# cube_atmega328.net
KiCad netlist of a schematic drawn in EAGLE
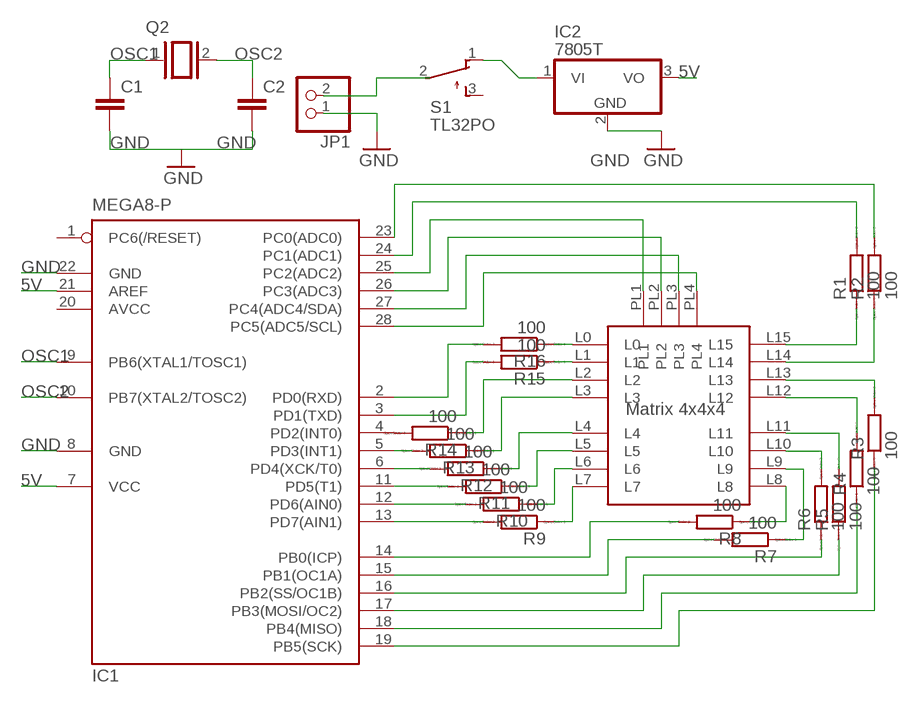
[diagram p0: schematic, sheet 1]

(export (version "E")
  (design (tool "Eeschema 10.0.6"))
  (components
    (comp (ref "C1")
      (value "C5/2.5")
      (footprint "eagle-import:C5B2.5")
      (libsource (lib "eagle-import") (part "C5/2.5"))
    )
    (comp (ref "C2")
      (value "C5/2.5")
      (footprint "eagle-import:C5B2.5")
      (libsource (lib "eagle-import") (part "C5/2.5"))
    )
    (comp (ref "IC1")
      (value "MEGA8-P")
      (footprint "eagle-import:DIL28-3")
      (libsource (lib "eagle-import") (part "MEGA8-P"))
    )
    (comp (ref "IC2")
      (value "7805T")
      (footprint "eagle-import:TO220H")
      (libsource (lib "eagle-import") (part "78T05"))
    )
    (comp (ref "JP1")
      (value "PINHD-1X2")
      (footprint "eagle-import:1X02")
      (libsource (lib "eagle-import") (part "PINHD-1X2"))
    )
    (comp (ref "Q2")
      (value "XTAL/S")
      (footprint "eagle-import:QS")
      (libsource (lib "eagle-import") (part "XTAL/S"))
    )
    (comp (ref "R1")
      (value "100")
      (footprint "eagle-import:0207_10")
      (libsource (lib "eagle-import") (part "R0207/10"))
    )
    (comp (ref "R2")
      (value "100")
      (footprint "eagle-import:0207_10")
      (libsource (lib "eagle-import") (part "R0207/10"))
    )
    (comp (ref "R3")
      (value "100")
      (footprint "eagle-import:0207_10")
      (libsource (lib "eagle-import") (part "R0207/10"))
    )
    (comp (ref "R4")
      (value "100")
      (footprint "eagle-import:0207_10")
      (libsource (lib "eagle-import") (part "R0207/10"))
    )
    (comp (ref "R5")
      (value "100")
      (footprint "eagle-import:0207_10")
      (libsource (lib "eagle-import") (part "R0207/10"))
    )
    (comp (ref "R6")
      (value "100")
      (footprint "eagle-import:0207_10")
      (libsource (lib "eagle-import") (part "R0207/10"))
    )
    (comp (ref "R7")
      (value "100")
      (footprint "eagle-import:0207_10")
      (libsource (lib "eagle-import") (part "R0207/10"))
    )
    (comp (ref "R8")
      (value "100")
      (footprint "eagle-import:0207_10")
      (libsource (lib "eagle-import") (part "R0207/10"))
    )
    (comp (ref "R9")
      (value "100")
      (footprint "eagle-import:0207_10")
      (libsource (lib "eagle-import") (part "R0207/10"))
    )
    (comp (ref "R10")
      (value "100")
      (footprint "eagle-import:0207_10")
      (libsource (lib "eagle-import") (part "R0207/10"))
    )
    (comp (ref "R11")
      (value "100")
      (footprint "eagle-import:0207_10")
      (libsource (lib "eagle-import") (part "R0207/10"))
    )
    (comp (ref "R12")
      (value "100")
      (footprint "eagle-import:0207_10")
      (libsource (lib "eagle-import") (part "R0207/10"))
    )
    (comp (ref "R13")
      (value "100")
      (footprint "eagle-import:0207_10")
      (libsource (lib "eagle-import") (part "R0207/10"))
    )
    (comp (ref "R14")
      (value "100")
      (footprint "eagle-import:0207_10")
      (libsource (lib "eagle-import") (part "R0207/10"))
    )
    (comp (ref "R15")
      (value "100")
      (footprint "eagle-import:0207_10")
      (libsource (lib "eagle-import") (part "R0207/10"))
    )
    (comp (ref "R16")
      (value "100")
      (footprint "eagle-import:0207_10")
      (libsource (lib "eagle-import") (part "R0207/10"))
    )
    (comp (ref "S1")
      (value "TL32PO")
      (footprint "eagle-import:TL3XPO")
      (libsource (lib "eagle-import") (part "TL32PO"))
    )
    (comp (ref "U$1")
      (value "LC4X4X4")
      (footprint "eagle-import:LC4X4X4")
      (libsource (lib "eagle-import") (part "LC4X4X4"))
    )
  )
  (nets
    (net (code "1") (name "/5V") (class "Default")
      (node (ref "IC1") (pin "21") (pinfunction "AREF_21") (pintype "passive"))
      (node (ref "IC1") (pin "7") (pinfunction "VCC_7") (pintype "power_in"))
      (node (ref "IC2") (pin "3") (pinfunction "VO_3") (pintype "passive"))
    )
    (net (code "2") (name "/AVCC") (class "Default")
      (node (ref "IC1") (pin "20") (pinfunction "AVCC_20") (pintype "power_in"))
    )
    (net (code "3") (name "/OSC1") (class "Default")
      (node (ref "C1") (pin "1") (pinfunction "1_1") (pintype "passive"))
      (node (ref "IC1") (pin "9") (pinfunction "PB6(XTAL1/TOSC1)_9") (pintype "bidirectional"))
      (node (ref "Q2") (pin "1") (pinfunction "1_1") (pintype "passive"))
    )
    (net (code "4") (name "/OSC2") (class "Default")
      (node (ref "C2") (pin "1") (pinfunction "1_1") (pintype "passive"))
      (node (ref "IC1") (pin "10") (pinfunction "PB7(XTAL2/TOSC2)_10") (pintype "bidirectional"))
      (node (ref "Q2") (pin "2") (pinfunction "2_2") (pintype "passive"))
    )
    (net (code "5") (name "GND") (class "Default")
      (node (ref "C1") (pin "2") (pinfunction "2_2") (pintype "passive"))
      (node (ref "C2") (pin "2") (pinfunction "2_2") (pintype "passive"))
      (node (ref "IC1") (pin "22") (pinfunction "GND_22") (pintype "power_in"))
      (node (ref "IC1") (pin "8") (pinfunction "GND_8") (pintype "power_in"))
      (node (ref "IC2") (pin "2") (pinfunction "GND_2") (pintype "passive"))
      (node (ref "JP1") (pin "1") (pinfunction "1_1") (pintype "passive"))
    )
    (net (code "6") (name "Net-(IC1-PB0(ICP))") (class "Default")
      (node (ref "IC1") (pin "14") (pinfunction "PB0(ICP)_14") (pintype "bidirectional"))
      (node (ref "R8") (pin "2") (pinfunction "2_2") (pintype "passive"))
    )
    (net (code "7") (name "Net-(IC1-PB1(OC1A))") (class "Default")
      (node (ref "IC1") (pin "15") (pinfunction "PB1(OC1A)_15") (pintype "bidirectional"))
      (node (ref "R7") (pin "2") (pinfunction "2_2") (pintype "passive"))
    )
    (net (code "8") (name "Net-(IC1-PB2(SS{slash}OC1B))") (class "Default")
      (node (ref "IC1") (pin "16") (pinfunction "PB2(SS/OC1B)_16") (pintype "bidirectional"))
      (node (ref "R6") (pin "1") (pinfunction "1_1") (pintype "passive"))
    )
    (net (code "9") (name "Net-(IC1-PB3(MOSI{slash}OC2))") (class "Default")
      (node (ref "IC1") (pin "17") (pinfunction "PB3(MOSI/OC2)_17") (pintype "bidirectional"))
      (node (ref "R5") (pin "1") (pinfunction "1_1") (pintype "passive"))
    )
    (net (code "10") (name "Net-(IC1-PB4(MISO))") (class "Default")
      (node (ref "IC1") (pin "18") (pinfunction "PB4(MISO)_18") (pintype "bidirectional"))
      (node (ref "R4") (pin "1") (pinfunction "1_1") (pintype "passive"))
    )
    (net (code "11") (name "Net-(IC1-PB5(SCK))") (class "Default")
      (node (ref "IC1") (pin "19") (pinfunction "PB5(SCK)_19") (pintype "bidirectional"))
      (node (ref "R3") (pin "1") (pinfunction "1_1") (pintype "passive"))
    )
    (net (code "12") (name "Net-(IC1-PC0(ADC0))") (class "Default")
      (node (ref "IC1") (pin "23") (pinfunction "PC0(ADC0)_23") (pintype "bidirectional"))
      (node (ref "R2") (pin "2") (pinfunction "2_2") (pintype "passive"))
    )
    (net (code "13") (name "Net-(IC1-PC1(ADC1))") (class "Default")
      (node (ref "IC1") (pin "24") (pinfunction "PC1(ADC1)_24") (pintype "bidirectional"))
      (node (ref "R1") (pin "2") (pinfunction "2_2") (pintype "passive"))
    )
    (net (code "14") (name "Net-(IC1-PC2(ADC2))") (class "Default")
      (node (ref "IC1") (pin "25") (pinfunction "PC2(ADC2)_25") (pintype "bidirectional"))
      (node (ref "U$1") (pin "PL1") (pinfunction "PL1_PL1") (pintype "bidirectional"))
    )
    (net (code "15") (name "Net-(IC1-PC3(ADC3))") (class "Default")
      (node (ref "IC1") (pin "26") (pinfunction "PC3(ADC3)_26") (pintype "bidirectional"))
      (node (ref "U$1") (pin "PL2") (pinfunction "PL2_PL2") (pintype "bidirectional"))
    )
    (net (code "16") (name "Net-(IC1-PC4(ADC4{slash}SDA))") (class "Default")
      (node (ref "IC1") (pin "27") (pinfunction "PC4(ADC4/SDA)_27") (pintype "bidirectional"))
      (node (ref "U$1") (pin "PL3") (pinfunction "PL3_PL3") (pintype "bidirectional"))
    )
    (net (code "17") (name "Net-(IC1-PC5(ADC5{slash}SCL))") (class "Default")
      (node (ref "IC1") (pin "28") (pinfunction "PC5(ADC5/SCL)_28") (pintype "bidirectional"))
      (node (ref "U$1") (pin "PL4") (pinfunction "PL4_PL4") (pintype "bidirectional"))
    )
    (net (code "18") (name "Net-(IC1-PD0(RXD))") (class "Default")
      (node (ref "IC1") (pin "2") (pinfunction "PD0(RXD)_2") (pintype "bidirectional"))
      (node (ref "R16") (pin "2") (pinfunction "2_2") (pintype "passive"))
    )
    (net (code "19") (name "Net-(IC1-PD1(TXD))") (class "Default")
      (node (ref "IC1") (pin "3") (pinfunction "PD1(TXD)_3") (pintype "bidirectional"))
      (node (ref "R15") (pin "2") (pinfunction "2_2") (pintype "passive"))
    )
    (net (code "20") (name "Net-(IC1-PD2(INT0))") (class "Default")
      (node (ref "IC1") (pin "4") (pinfunction "PD2(INT0)_4") (pintype "bidirectional"))
      (node (ref "R14") (pin "2") (pinfunction "2_2") (pintype "passive"))
    )
    (net (code "21") (name "Net-(IC1-PD3(INT1))") (class "Default")
      (node (ref "IC1") (pin "5") (pinfunction "PD3(INT1)_5") (pintype "bidirectional"))
      (node (ref "R13") (pin "2") (pinfunction "2_2") (pintype "passive"))
    )
    (net (code "22") (name "Net-(IC1-PD4(XCK{slash}T0))") (class "Default")
      (node (ref "IC1") (pin "6") (pinfunction "PD4(XCK/T0)_6") (pintype "bidirectional"))
      (node (ref "R12") (pin "2") (pinfunction "2_2") (pintype "passive"))
    )
    (net (code "23") (name "Net-(IC1-PD5(T1))") (class "Default")
      (node (ref "IC1") (pin "11") (pinfunction "PD5(T1)_11") (pintype "bidirectional"))
      (node (ref "R11") (pin "2") (pinfunction "2_2") (pintype "passive"))
    )
    (net (code "24") (name "Net-(IC1-PD6(AIN0))") (class "Default")
      (node (ref "IC1") (pin "12") (pinfunction "PD6(AIN0)_12") (pintype "bidirectional"))
      (node (ref "R10") (pin "2") (pinfunction "2_2") (pintype "passive"))
    )
    (net (code "25") (name "Net-(IC1-PD7(AIN1))") (class "Default")
      (node (ref "IC1") (pin "13") (pinfunction "PD7(AIN1)_13") (pintype "bidirectional"))
      (node (ref "R9") (pin "2") (pinfunction "2_2") (pintype "passive"))
    )
    (net (code "26") (name "Net-(IC2-VI)") (class "Default")
      (node (ref "IC2") (pin "1") (pinfunction "VI_1") (pintype "input"))
      (node (ref "S1") (pin "1") (pinfunction "O_1") (pintype "passive"))
    )
    (net (code "27") (name "Net-(R1-Pad1)") (class "Default")
      (node (ref "R1") (pin "1") (pinfunction "1_1") (pintype "passive"))
      (node (ref "U$1") (pin "L15") (pinfunction "L15_L15") (pintype "bidirectional"))
    )
    (net (code "28") (name "Net-(R2-Pad1)") (class "Default")
      (node (ref "R2") (pin "1") (pinfunction "1_1") (pintype "passive"))
      (node (ref "U$1") (pin "L14") (pinfunction "L14_L14") (pintype "bidirectional"))
    )
    (net (code "29") (name "Net-(R3-Pad2)") (class "Default")
      (node (ref "R3") (pin "2") (pinfunction "2_2") (pintype "passive"))
      (node (ref "U$1") (pin "L13") (pinfunction "L13_L13") (pintype "bidirectional"))
    )
    (net (code "30") (name "Net-(R4-Pad2)") (class "Default")
      (node (ref "R4") (pin "2") (pinfunction "2_2") (pintype "passive"))
      (node (ref "U$1") (pin "L12") (pinfunction "L12_L12") (pintype "bidirectional"))
    )
    (net (code "31") (name "Net-(R5-Pad2)") (class "Default")
      (node (ref "R5") (pin "2") (pinfunction "2_2") (pintype "passive"))
      (node (ref "U$1") (pin "L11") (pinfunction "L11_L11") (pintype "bidirectional"))
    )
    (net (code "32") (name "Net-(R6-Pad2)") (class "Default")
      (node (ref "R6") (pin "2") (pinfunction "2_2") (pintype "passive"))
      (node (ref "U$1") (pin "L10") (pinfunction "L10_L10") (pintype "bidirectional"))
    )
    (net (code "33") (name "Net-(R7-Pad1)") (class "Default")
      (node (ref "R7") (pin "1") (pinfunction "1_1") (pintype "passive"))
      (node (ref "U$1") (pin "L9") (pinfunction "L9_L9") (pintype "bidirectional"))
    )
    (net (code "34") (name "Net-(R8-Pad1)") (class "Default")
      (node (ref "R8") (pin "1") (pinfunction "1_1") (pintype "passive"))
      (node (ref "U$1") (pin "L8") (pinfunction "L8_L8") (pintype "bidirectional"))
    )
    (net (code "35") (name "Net-(R9-Pad1)") (class "Default")
      (node (ref "R9") (pin "1") (pinfunction "1_1") (pintype "passive"))
      (node (ref "U$1") (pin "L7") (pinfunction "L7_L7") (pintype "bidirectional"))
    )
    (net (code "36") (name "Net-(R10-Pad1)") (class "Default")
      (node (ref "R10") (pin "1") (pinfunction "1_1") (pintype "passive"))
      (node (ref "U$1") (pin "L6") (pinfunction "L6_L6") (pintype "bidirectional"))
    )
    (net (code "37") (name "Net-(R11-Pad1)") (class "Default")
      (node (ref "R11") (pin "1") (pinfunction "1_1") (pintype "passive"))
      (node (ref "U$1") (pin "L5") (pinfunction "L5_L5") (pintype "bidirectional"))
    )
    (net (code "38") (name "Net-(R12-Pad1)") (class "Default")
      (node (ref "R12") (pin "1") (pinfunction "1_1") (pintype "passive"))
      (node (ref "U$1") (pin "L4") (pinfunction "L4_L4") (pintype "bidirectional"))
    )
    (net (code "39") (name "Net-(R13-Pad1)") (class "Default")
      (node (ref "R13") (pin "1") (pinfunction "1_1") (pintype "passive"))
      (node (ref "U$1") (pin "L3") (pinfunction "L3_L3") (pintype "bidirectional"))
    )
    (net (code "40") (name "Net-(R14-Pad1)") (class "Default")
      (node (ref "R14") (pin "1") (pinfunction "1_1") (pintype "passive"))
      (node (ref "U$1") (pin "L2") (pinfunction "L2_L2") (pintype "bidirectional"))
    )
    (net (code "41") (name "Net-(R15-Pad1)") (class "Default")
      (node (ref "R15") (pin "1") (pinfunction "1_1") (pintype "passive"))
      (node (ref "U$1") (pin "L1") (pinfunction "L1_L1") (pintype "bidirectional"))
    )
    (net (code "42") (name "Net-(R16-Pad1)") (class "Default")
      (node (ref "R16") (pin "1") (pinfunction "1_1") (pintype "passive"))
      (node (ref "U$1") (pin "L0") (pinfunction "L0_L0") (pintype "bidirectional"))
    )
    (net (code "43") (name "unconnected-(IC1-PC6({slash}RESET)-Pad1)") (class "Default")
      (node (ref "IC1") (pin "1") (pinfunction "PC6(/RESET)_1") (pintype "bidirectional"))
    )
    (net (code "44") (name "unconnected-(JP1-Pad2)") (class "Default")
      (node (ref "JP1") (pin "2") (pinfunction "2_2") (pintype "passive"))
    )
    (net (code "45") (name "unconnected-(S1-P-Pad2)") (class "Default")
      (node (ref "S1") (pin "2") (pinfunction "P_2") (pintype "passive"))
    )
    (net (code "46") (name "unconnected-(S1-S-Pad3)") (class "Default")
      (node (ref "S1") (pin "3") (pinfunction "S_3") (pintype "passive"))
    )
  )
)
